# CW340_Clocks.net
KiCad netlist of a schematic drawn in Altium Designer
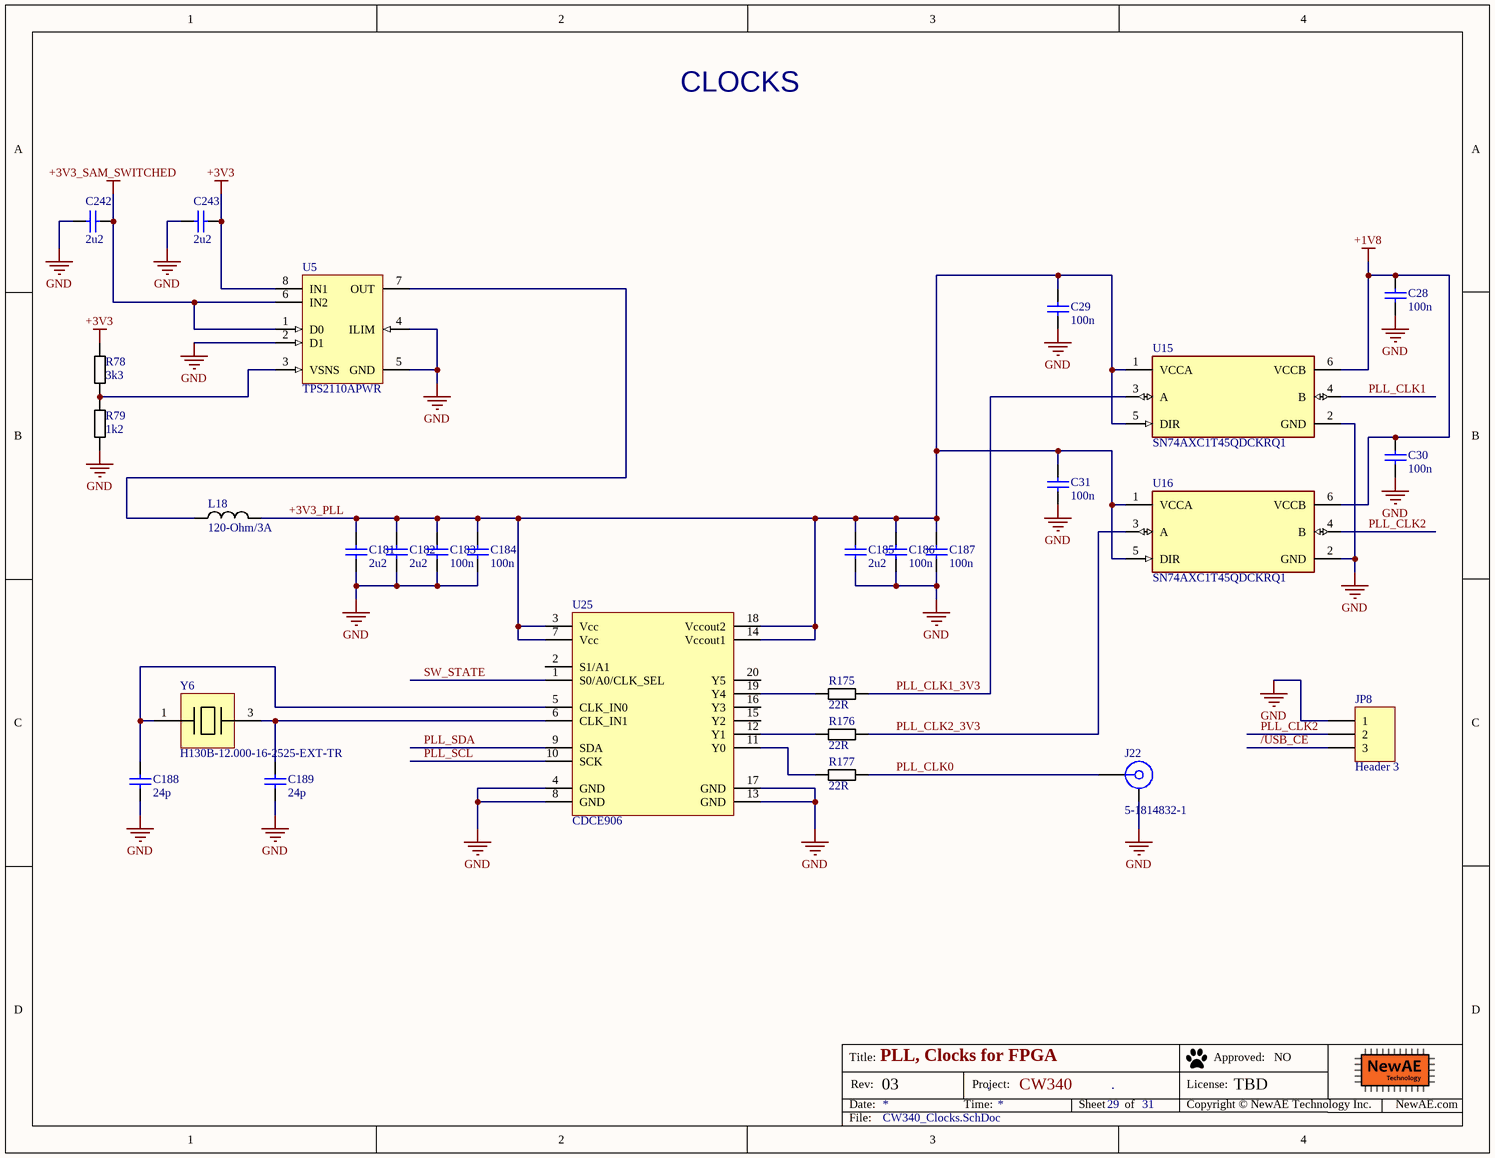
[diagram p0: CW340_Clocks.SchDoc]

(export (version "E")
  (design (tool "Eeschema 10.0.6"))
  (components
    (comp (ref "C28")
      (value "100n")
      (footprint "CAPC0402_M")
      (description "100n, 0402")
      (fields (field (name "PART NUMBER") "CCHIP-100n-0402"))
      (libsource (lib "NewAE_AltiumLib") (part "CAP"))
    )
    (comp (ref "C29")
      (value "100n")
      (footprint "CAPC0402_M")
      (description "100n, 0402")
      (fields (field (name "PART NUMBER") "CCHIP-100n-0402"))
      (libsource (lib "NewAE_AltiumLib") (part "CAP"))
    )
    (comp (ref "C30")
      (value "100n")
      (footprint "CAPC0402_M")
      (description "100n, 0402")
      (fields (field (name "PART NUMBER") "CCHIP-100n-0402"))
      (libsource (lib "NewAE_AltiumLib") (part "CAP"))
    )
    (comp (ref "C31")
      (value "100n")
      (footprint "CAPC0402_M")
      (description "100n, 0402")
      (fields (field (name "PART NUMBER") "CCHIP-100n-0402"))
      (libsource (lib "NewAE_AltiumLib") (part "CAP"))
    )
    (comp (ref "C181")
      (value "2u2")
      (footprint "CAPC0603_M")
      (description "2u2, 0603")
      (fields (field (name "PART NUMBER") "CCHIP-2u2-0603-16V"))
      (libsource (lib "NewAE_AltiumLib") (part "CAP"))
    )
    (comp (ref "C182")
      (value "2u2")
      (footprint "CAPC0603_M")
      (description "2u2, 0603")
      (fields (field (name "PART NUMBER") "CCHIP-2u2-0603-16V"))
      (libsource (lib "NewAE_AltiumLib") (part "CAP"))
    )
    (comp (ref "C183")
      (value "100n")
      (footprint "CAPC0402_M")
      (description "100n, 0402")
      (fields (field (name "PART NUMBER") "CCHIP-100n-0402"))
      (libsource (lib "NewAE_AltiumLib") (part "CAP"))
    )
    (comp (ref "C184")
      (value "100n")
      (footprint "CAPC0402_M")
      (description "100n, 0402")
      (fields (field (name "PART NUMBER") "CCHIP-100n-0402"))
      (libsource (lib "NewAE_AltiumLib") (part "CAP"))
    )
    (comp (ref "C185")
      (value "2u2")
      (footprint "CAPC0603_M")
      (description "2u2, 0603")
      (fields (field (name "PART NUMBER") "CCHIP-2u2-0603-16V"))
      (libsource (lib "NewAE_AltiumLib") (part "CAP"))
    )
    (comp (ref "C186")
      (value "100n")
      (footprint "CAPC0402_M")
      (description "100n, 0402")
      (fields (field (name "PART NUMBER") "CCHIP-100n-0402"))
      (libsource (lib "NewAE_AltiumLib") (part "CAP"))
    )
    (comp (ref "C187")
      (value "100n")
      (footprint "CAPC0402_M")
      (description "100n, 0402")
      (fields (field (name "PART NUMBER") "CCHIP-100n-0402"))
      (libsource (lib "NewAE_AltiumLib") (part "CAP"))
    )
    (comp (ref "C188")
      (value "24p")
      (footprint "CAPC0402_M")
      (description "24p, 0402")
      (fields (field (name "PART NUMBER") "CCHIP-24p-0402"))
      (libsource (lib "NewAE_AltiumLib") (part "CAP"))
    )
    (comp (ref "C189")
      (value "24p")
      (footprint "CAPC0402_M")
      (description "24p, 0402")
      (fields (field (name "PART NUMBER") "CCHIP-24p-0402"))
      (libsource (lib "NewAE_AltiumLib") (part "CAP"))
    )
    (comp (ref "C242")
      (value "2u2")
      (footprint "CAPC0603_M")
      (description "2u2, 0603")
      (fields (field (name "PART NUMBER") "CCHIP-2u2-0603-16V"))
      (libsource (lib "NewAE_AltiumLib") (part "CAP"))
    )
    (comp (ref "C243")
      (value "2u2")
      (footprint "CAPC0603_M")
      (description "2u2, 0603")
      (fields (field (name "PART NUMBER") "CCHIP-2u2-0603-16V"))
      (libsource (lib "NewAE_AltiumLib") (part "CAP"))
    )
    (comp (ref "J22")
      (value "5-1814832-1")
      (footprint "SMA_VERT_1.65MMHOLE")
      (description "SMA, Vert")
      (libsource (lib "NewAE_AltiumLib") (part "5-1814832-1"))
    )
    (comp (ref "JP8")
      (value "Header 3")
      (footprint "HDR1X3")
      (description "Header, 3-Pin")
      (fields (field (name "PUBLISHER") "Altium Limited"))
      (libsource (lib "Miscellaneous Connectors") (part "Header 3"))
    )
    (comp (ref "L18")
      (value "120-Ohm/3A")
      (footprint "IND_0603")
      (description "120 Ohm @ 100 MHz, 3A rated FB")
      (fields (field (name "PART NUMBER") "FBCHIP-120R-0603"))
      (libsource (lib "NewAE_AltiumLib") (part "IND"))
    )
    (comp (ref "R78")
      (value "3k3")
      (footprint "RESC1005X40N")
      (description "3k3 res, 0402, 1%, 1/16W")
      (fields (field (name "PART NUMBER") "RCHIP-3K3-0402") (field (name "TOLERANCE") "1%"))
      (libsource (lib "") (part "RES-EU_1"))
    )
    (comp (ref "R79")
      (value "1k2")
      (footprint "RESC1005X40N")
      (description "1k2 res, 0402, 1%, 1/16W")
      (fields (field (name "PART NUMBER") "RCHIP-1K2-0402") (field (name "TOLERANCE") "1%"))
      (libsource (lib "") (part "RES-EU_1"))
    )
    (comp (ref "R175")
      (value "22R")
      (footprint "RESC1005X40N")
      (description "22R res, 0402, 1%, 1/16W")
      (fields (field (name "PART NUMBER") "RCHIP-22R-0402") (field (name "TOLERANCE") "1%"))
      (libsource (lib "NewAE_AltiumLib") (part "RES-EU"))
    )
    (comp (ref "R176")
      (value "22R")
      (footprint "RESC1005X40N")
      (description "22R res, 0402, 1%, 1/16W")
      (fields (field (name "PART NUMBER") "RCHIP-22R-0402") (field (name "TOLERANCE") "1%"))
      (libsource (lib "NewAE_AltiumLib") (part "RES-EU"))
    )
    (comp (ref "R177")
      (value "22R")
      (footprint "RESC1005X40N")
      (description "22R res, 0402, 1%, 1/16W")
      (fields (field (name "PART NUMBER") "RCHIP-22R-0402") (field (name "TOLERANCE") "1%"))
      (libsource (lib "NewAE_AltiumLib") (part "RES-EU"))
    )
    (comp (ref "U5")
      (value "TPS2110APWR")
      (footprint "PW0008A_L")
      (fields (field (name "MANUFACTURER") "Texas Instruments"))
      (libsource (lib "Altium Content Vault") (part "TI-TPS2110APW8"))
    )
    (comp (ref "U15")
      (value "SN74AXC1T45QDCKRQ1")
      (footprint "FP-DCK0006A-MFG")
      (description "IC LOGIC BUFFER/DRIVER")
      (libsource (lib "Altium Content Vault") (part "f9f0ad90c916d56c07594708ea855bb"))
    )
    (comp (ref "U16")
      (value "SN74AXC1T45QDCKRQ1")
      (footprint "FP-DCK0006A-MFG")
      (description "IC LOGIC BUFFER/DRIVER")
      (libsource (lib "Altium Content Vault") (part "f9f0ad90c916d56c07594708ea855bb"))
    )
    (comp (ref "U25")
      (value "CDCE906")
      (footprint "TSSOP065-20-PW")
      (description "IC 3-PLL SYNTH/MULT/DIV 20-TSSOP")
      (fields (field (name "PART NUMBER") "CDCE906PW"))
      (libsource (lib "NewAE_AltiumLib") (part "CDCE906"))
    )
    (comp (ref "Y6")
      (value "H130B-12.000-16-2525-EXT-TR")
      (footprint "5x3.2mm XTAL")
      (description "12MHz ±25ppm Crystal 16pF 35 Ohms 4-SMD, No Lead")
      (fields (field (name "MANUFACTURER PART NUMBER") "H130B-12.000-16-2525-EXT-TR"))
      (libsource (lib "NewAE_AltiumLib") (part "H130B-12.000-16-2525-EXT-TR"))
    )
  )
  (nets
    (net (code "1") (name "+1V8") (class "Default")
      (node (ref "C28") (pin "1") (pinfunction "1_1") (pintype "passive"))
      (node (ref "C30") (pin "1") (pinfunction "1_1") (pintype "passive"))
      (node (ref "U15") (pin "6") (pinfunction "VCCB_6") (pintype "power_in"))
      (node (ref "U16") (pin "6") (pinfunction "VCCB_6") (pintype "power_in"))
    )
    (net (code "2") (name "+3V3") (class "Default")
      (node (ref "C243") (pin "2") (pinfunction "2_2") (pintype "passive"))
      (node (ref "R78") (pin "1") (pinfunction "1_1") (pintype "passive"))
      (node (ref "U5") (pin "8") (pinfunction "IN1_8") (pintype "power_in"))
    )
    (net (code "3") (name "+3V3_SAM_SWITCHED") (class "Default")
      (node (ref "C242") (pin "2") (pinfunction "2_2") (pintype "passive"))
      (node (ref "U5") (pin "1") (pinfunction "D0_1") (pintype "input"))
      (node (ref "U5") (pin "6") (pinfunction "IN2_6") (pintype "power_in"))
    )
    (net (code "4") (name "/+3V3_PLL") (class "Default")
      (node (ref "C181") (pin "1") (pinfunction "1_1") (pintype "passive"))
      (node (ref "C182") (pin "1") (pinfunction "1_1") (pintype "passive"))
      (node (ref "C183") (pin "1") (pinfunction "1_1") (pintype "passive"))
      (node (ref "C184") (pin "1") (pinfunction "1_1") (pintype "passive"))
      (node (ref "C185") (pin "1") (pinfunction "1_1") (pintype "passive"))
      (node (ref "C186") (pin "1") (pinfunction "1_1") (pintype "passive"))
      (node (ref "C187") (pin "1") (pinfunction "1_1") (pintype "passive"))
      (node (ref "C29") (pin "1") (pinfunction "1_1") (pintype "passive"))
      (node (ref "C31") (pin "1") (pinfunction "1_1") (pintype "passive"))
      (node (ref "L18") (pin "2") (pinfunction "2_2") (pintype "passive"))
      (node (ref "U15") (pin "1") (pinfunction "VCCA_1") (pintype "power_in"))
      (node (ref "U15") (pin "5") (pinfunction "DIR_5") (pintype "input"))
      (node (ref "U16") (pin "1") (pinfunction "VCCA_1") (pintype "power_in"))
      (node (ref "U16") (pin "5") (pinfunction "DIR_5") (pintype "input"))
      (node (ref "U25") (pin "14") (pinfunction "Vccout1_14") (pintype "passive"))
      (node (ref "U25") (pin "18") (pinfunction "Vccout2_18") (pintype "passive"))
      (node (ref "U25") (pin "3") (pinfunction "Vcc_3") (pintype "passive"))
      (node (ref "U25") (pin "7") (pinfunction "Vcc_7") (pintype "passive"))
    )
    (net (code "5") (name "/PLL_CLK0") (class "Default")
      (node (ref "J22") (pin "1") (pinfunction "1_1") (pintype "passive"))
      (node (ref "R177") (pin "2") (pinfunction "2_2") (pintype "passive"))
    )
    (net (code "6") (name "/PLL_CLK1") (class "Default")
      (node (ref "U15") (pin "4") (pinfunction "B_4") (pintype "bidirectional"))
    )
    (net (code "7") (name "/PLL_CLK1_3V3") (class "Default")
      (node (ref "R175") (pin "2") (pinfunction "2_2") (pintype "passive"))
      (node (ref "U15") (pin "3") (pinfunction "A_3") (pintype "bidirectional"))
    )
    (net (code "8") (name "/PLL_CLK2") (class "Default")
      (node (ref "JP8") (pin "2") (pinfunction "2_2") (pintype "passive"))
      (node (ref "U16") (pin "4") (pinfunction "B_4") (pintype "bidirectional"))
    )
    (net (code "9") (name "/PLL_CLK2_3V3") (class "Default")
      (node (ref "R176") (pin "2") (pinfunction "2_2") (pintype "passive"))
      (node (ref "U16") (pin "3") (pinfunction "A_3") (pintype "bidirectional"))
    )
    (net (code "10") (name "/PLL_SCL") (class "Default")
      (node (ref "U25") (pin "10") (pinfunction "SCK_10") (pintype "passive"))
    )
    (net (code "11") (name "/PLL_SDA") (class "Default")
      (node (ref "U25") (pin "9") (pinfunction "SDA_9") (pintype "passive"))
    )
    (net (code "12") (name "/SW_STATE") (class "Default")
      (node (ref "U25") (pin "1") (pinfunction "S0/A0/CLK_SEL_1") (pintype "passive"))
    )
    (net (code "13") (name "/{slash}USB_CE") (class "Default")
      (node (ref "JP8") (pin "3") (pinfunction "3_3") (pintype "passive"))
    )
    (net (code "14") (name "GND") (class "Default")
      (node (ref "C181") (pin "2") (pinfunction "2_2") (pintype "passive"))
      (node (ref "C182") (pin "2") (pinfunction "2_2") (pintype "passive"))
      (node (ref "C183") (pin "2") (pinfunction "2_2") (pintype "passive"))
      (node (ref "C184") (pin "2") (pinfunction "2_2") (pintype "passive"))
      (node (ref "C185") (pin "2") (pinfunction "2_2") (pintype "passive"))
      (node (ref "C186") (pin "2") (pinfunction "2_2") (pintype "passive"))
      (node (ref "C187") (pin "2") (pinfunction "2_2") (pintype "passive"))
      (node (ref "C188") (pin "2") (pinfunction "2_2") (pintype "passive"))
      (node (ref "C189") (pin "2") (pinfunction "2_2") (pintype "passive"))
      (node (ref "C242") (pin "1") (pinfunction "1_1") (pintype "passive"))
      (node (ref "C243") (pin "1") (pinfunction "1_1") (pintype "passive"))
      (node (ref "C28") (pin "2") (pinfunction "2_2") (pintype "passive"))
      (node (ref "C29") (pin "2") (pinfunction "2_2") (pintype "passive"))
      (node (ref "C30") (pin "2") (pinfunction "2_2") (pintype "passive"))
      (node (ref "C31") (pin "2") (pinfunction "2_2") (pintype "passive"))
      (node (ref "J22") (pin "MH") (pinfunction "MH_MH") (pintype "passive"))
      (node (ref "JP8") (pin "1") (pinfunction "1_1") (pintype "passive"))
      (node (ref "R79") (pin "2") (pinfunction "2_2") (pintype "passive"))
      (node (ref "U15") (pin "2") (pinfunction "GND_2") (pintype "power_in"))
      (node (ref "U16") (pin "2") (pinfunction "GND_2") (pintype "power_in"))
      (node (ref "U25") (pin "13") (pinfunction "GND_13") (pintype "passive"))
      (node (ref "U25") (pin "17") (pinfunction "GND_17") (pintype "passive"))
      (node (ref "U25") (pin "4") (pinfunction "GND_4") (pintype "passive"))
      (node (ref "U25") (pin "8") (pinfunction "GND_8") (pintype "passive"))
      (node (ref "U5") (pin "2") (pinfunction "D1_2") (pintype "input"))
      (node (ref "U5") (pin "4") (pinfunction "ILIM_4") (pintype "input"))
      (node (ref "U5") (pin "5") (pinfunction "GND_5") (pintype "power_in"))
    )
    (net (code "15") (name "Net-(U5-OUT)") (class "Default")
      (node (ref "L18") (pin "1") (pinfunction "1_1") (pintype "passive"))
      (node (ref "U5") (pin "7") (pinfunction "OUT_7") (pintype "power_in"))
    )
    (net (code "16") (name "Net-(U5-VSNS)") (class "Default")
      (node (ref "R78") (pin "2") (pinfunction "2_2") (pintype "passive"))
      (node (ref "R79") (pin "1") (pinfunction "1_1") (pintype "passive"))
      (node (ref "U5") (pin "3") (pinfunction "VSNS_3") (pintype "input"))
    )
    (net (code "17") (name "Net-(U25-CLK_IN0)") (class "Default")
      (node (ref "C188") (pin "1") (pinfunction "1_1") (pintype "passive"))
      (node (ref "U25") (pin "5") (pinfunction "CLK_IN0_5") (pintype "passive"))
      (node (ref "Y6") (pin "1") (pinfunction "1_1") (pintype "passive"))
    )
    (net (code "18") (name "Net-(U25-CLK_IN1)") (class "Default")
      (node (ref "C189") (pin "1") (pinfunction "1_1") (pintype "passive"))
      (node (ref "U25") (pin "6") (pinfunction "CLK_IN1_6") (pintype "passive"))
      (node (ref "Y6") (pin "3") (pinfunction "3_3") (pintype "passive"))
    )
    (net (code "19") (name "Net-(U25-Y0)") (class "Default")
      (node (ref "R177") (pin "1") (pinfunction "1_1") (pintype "passive"))
      (node (ref "U25") (pin "11") (pinfunction "Y0_11") (pintype "passive"))
    )
    (net (code "20") (name "Net-(U25-Y1)") (class "Default")
      (node (ref "R176") (pin "1") (pinfunction "1_1") (pintype "passive"))
      (node (ref "U25") (pin "12") (pinfunction "Y1_12") (pintype "passive"))
    )
    (net (code "21") (name "Net-(U25-Y4)") (class "Default")
      (node (ref "R175") (pin "1") (pinfunction "1_1") (pintype "passive"))
      (node (ref "U25") (pin "19") (pinfunction "Y4_19") (pintype "passive"))
    )
    (net (code "22") (name "unconnected-(U25-S1{slash}A1-Pad2)") (class "Default")
      (node (ref "U25") (pin "2") (pinfunction "S1/A1_2") (pintype "passive"))
    )
    (net (code "23") (name "unconnected-(U25-Y2-Pad15)") (class "Default")
      (node (ref "U25") (pin "15") (pinfunction "Y2_15") (pintype "passive"))
    )
    (net (code "24") (name "unconnected-(U25-Y3-Pad16)") (class "Default")
      (node (ref "U25") (pin "16") (pinfunction "Y3_16") (pintype "passive"))
    )
    (net (code "25") (name "unconnected-(U25-Y5-Pad20)") (class "Default")
      (node (ref "U25") (pin "20") (pinfunction "Y5_20") (pintype "passive"))
    )
  )
)
